# RGB-LED.net
KiCad netlist of a schematic drawn in Altium Designer
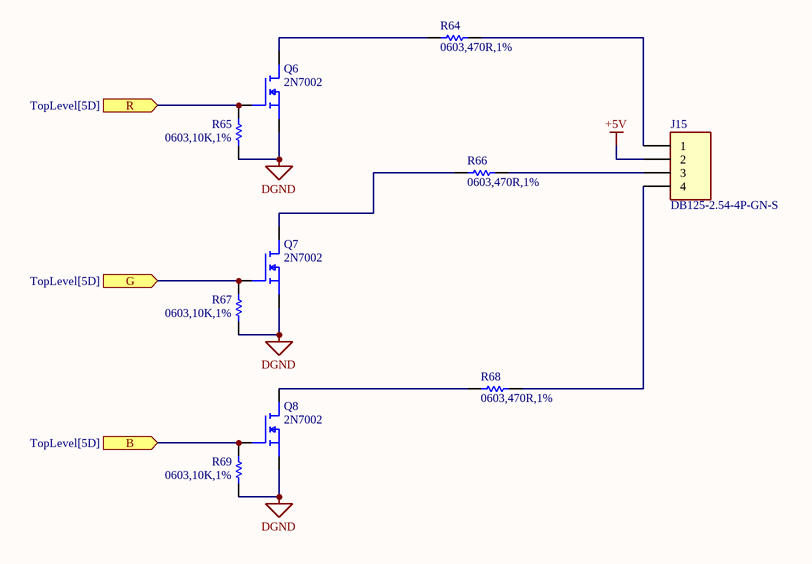
[diagram p0: RGB-LED.SchDoc]

(export (version "E")
  (design (tool "Eeschema 10.0.6"))
  (components
    (comp (ref "J15")
      (value "DB125-2.54-4P-GN-S")
      (footprint "DB125-2_54-4P-GN")
      (description "4 Position Wire to Board Terminal Block Through Hole 2.54mm")
      (fields (field (name "LCSC PART #") "C918122"))
      (libsource (lib "flight-controller") (part "DB125-2.54-4P-GN-S"))
    )
    (comp (ref "Q6")
      (value "2N7002")
      (footprint "SOT95P230X110-3N")
      (description "N-Channel 60V 300mA 830mW Surface Mount SOT-23")
      (fields (field (name "LCSC PART #") "C8545"))
      (libsource (lib "flight-controller") (part "2N7002"))
    )
    (comp (ref "Q7")
      (value "2N7002")
      (footprint "SOT95P230X110-3N")
      (description "N-Channel 60V 300mA 830mW Surface Mount SOT-23")
      (fields (field (name "LCSC PART #") "C8545"))
      (libsource (lib "flight-controller") (part "2N7002"))
    )
    (comp (ref "Q8")
      (value "2N7002")
      (footprint "SOT95P230X110-3N")
      (description "N-Channel 60V 300mA 830mW Surface Mount SOT-23")
      (fields (field (name "LCSC PART #") "C8545"))
      (libsource (lib "flight-controller") (part "2N7002"))
    )
    (comp (ref "R64")
      (value "0603,470R,1%")
      (footprint "RESC1608X90N")
      (fields (field (name "LCSC PART #") "C23179") (field (name "MANU PART #") "0603WAF4700T5E"))
      (libsource (lib "flight-controller") (part "0603WAF4700T5E"))
    )
    (comp (ref "R65")
      (value "0603,10K,1%")
      (footprint "RESC1608X90N")
      (description "100mW Thick Film Resistor 75V ±100ppm/℃ ±1% 10kΩ 0603 Chip Resistor - Surface Mount ROHS")
      (fields (field (name "LCSC PART #") "C25804") (field (name "MANU PART #") "0603WAF1002T5E"))
      (libsource (lib "flight-controller") (part "0603WAF1002T5E"))
    )
    (comp (ref "R66")
      (value "0603,470R,1%")
      (footprint "RESC1608X90N")
      (fields (field (name "LCSC PART #") "C23179") (field (name "MANU PART #") "0603WAF4700T5E"))
      (libsource (lib "flight-controller") (part "0603WAF4700T5E"))
    )
    (comp (ref "R67")
      (value "0603,10K,1%")
      (footprint "RESC1608X90N")
      (description "100mW Thick Film Resistor 75V ±100ppm/℃ ±1% 10kΩ 0603 Chip Resistor - Surface Mount ROHS")
      (fields (field (name "LCSC PART #") "C25804") (field (name "MANU PART #") "0603WAF1002T5E"))
      (libsource (lib "flight-controller") (part "0603WAF1002T5E"))
    )
    (comp (ref "R68")
      (value "0603,470R,1%")
      (footprint "RESC1608X90N")
      (fields (field (name "LCSC PART #") "C23179") (field (name "MANU PART #") "0603WAF4700T5E"))
      (libsource (lib "flight-controller") (part "0603WAF4700T5E"))
    )
    (comp (ref "R69")
      (value "0603,10K,1%")
      (footprint "RESC1608X90N")
      (description "100mW Thick Film Resistor 75V ±100ppm/℃ ±1% 10kΩ 0603 Chip Resistor - Surface Mount ROHS")
      (fields (field (name "LCSC PART #") "C25804") (field (name "MANU PART #") "0603WAF1002T5E"))
      (libsource (lib "flight-controller") (part "0603WAF1002T5E"))
    )
  )
  (nets
    (net (code "1") (name "+5V") (class "Default")
      (node (ref "J15") (pin "2") (pinfunction "2_2") (pintype "passive"))
    )
    (net (code "2") (name "/B") (class "Default")
      (node (ref "Q8") (pin "1") (pinfunction "G_1") (pintype "passive"))
      (node (ref "R69") (pin "2") (pinfunction "2_2") (pintype "passive"))
    )
    (net (code "3") (name "/G") (class "Default")
      (node (ref "Q7") (pin "1") (pinfunction "G_1") (pintype "passive"))
      (node (ref "R67") (pin "2") (pinfunction "2_2") (pintype "passive"))
    )
    (net (code "4") (name "/R") (class "Default")
      (node (ref "Q6") (pin "1") (pinfunction "G_1") (pintype "passive"))
      (node (ref "R65") (pin "2") (pinfunction "2_2") (pintype "passive"))
    )
    (net (code "5") (name "DGND") (class "Default")
      (node (ref "Q6") (pin "2") (pinfunction "S_2") (pintype "passive"))
      (node (ref "Q7") (pin "2") (pinfunction "S_2") (pintype "passive"))
      (node (ref "Q8") (pin "2") (pinfunction "S_2") (pintype "passive"))
      (node (ref "R65") (pin "1") (pinfunction "1_1") (pintype "passive"))
      (node (ref "R67") (pin "1") (pinfunction "1_1") (pintype "passive"))
      (node (ref "R69") (pin "1") (pinfunction "1_1") (pintype "passive"))
    )
    (net (code "6") (name "Net-(J15-Pad1)") (class "Default")
      (node (ref "J15") (pin "1") (pinfunction "1_1") (pintype "passive"))
      (node (ref "R64") (pin "2") (pinfunction "2_2") (pintype "passive"))
    )
    (net (code "7") (name "Net-(J15-Pad3)") (class "Default")
      (node (ref "J15") (pin "3") (pinfunction "3_3") (pintype "passive"))
      (node (ref "R66") (pin "2") (pinfunction "2_2") (pintype "passive"))
    )
    (net (code "8") (name "Net-(J15-Pad4)") (class "Default")
      (node (ref "J15") (pin "4") (pinfunction "4_4") (pintype "passive"))
      (node (ref "R68") (pin "2") (pinfunction "2_2") (pintype "passive"))
    )
    (net (code "9") (name "Net-(Q6-D)") (class "Default")
      (node (ref "Q6") (pin "3") (pinfunction "D_3") (pintype "passive"))
      (node (ref "R64") (pin "1") (pinfunction "1_1") (pintype "passive"))
    )
    (net (code "10") (name "Net-(Q7-D)") (class "Default")
      (node (ref "Q7") (pin "3") (pinfunction "D_3") (pintype "passive"))
      (node (ref "R66") (pin "1") (pinfunction "1_1") (pintype "passive"))
    )
    (net (code "11") (name "Net-(Q8-D)") (class "Default")
      (node (ref "Q8") (pin "3") (pinfunction "D_3") (pintype "passive"))
      (node (ref "R68") (pin "1") (pinfunction "1_1") (pintype "passive"))
    )
  )
)
